# Lesson_05.net
KiCad netlist of a schematic drawn in Altium Designer
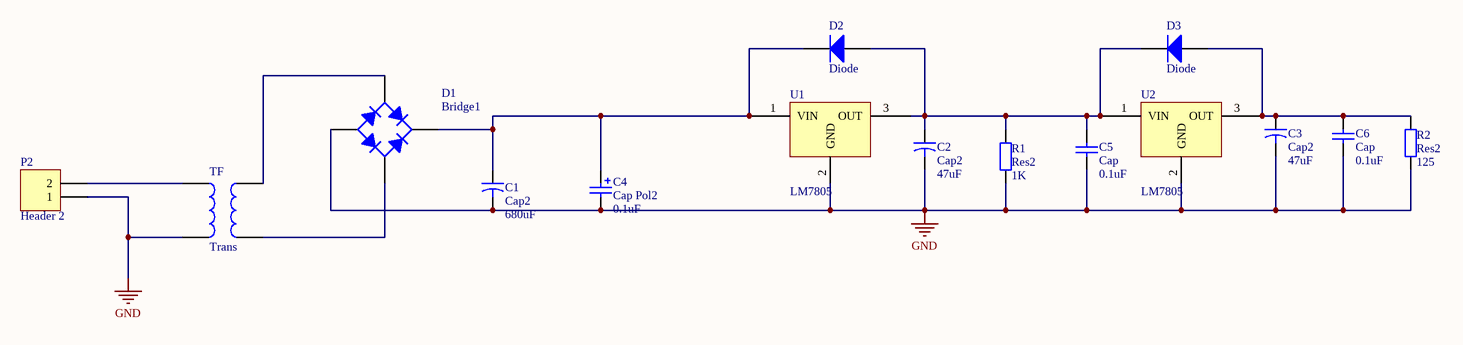
[diagram p0: Lesson_05.SchDoc]

(export (version "E")
  (design (tool "Eeschema 10.0.6"))
  (components
    (comp (ref "C1")
      (value "Cap2")
      (footprint "CAPR5-4X5")
      (description "Capacitor")
      (fields (field (name "ALTIUM_VALUE") "680uF") (field (name "PUBLISHER") "Altium Limited"))
      (libsource (lib "Miscellaneous Devices") (part "Cap2"))
    )
    (comp (ref "C2")
      (value "Cap2")
      (footprint "CAPR5-4X5")
      (description "Capacitor")
      (fields (field (name "ALTIUM_VALUE") "47uF") (field (name "PUBLISHER") "Altium Limited"))
      (libsource (lib "Miscellaneous Devices") (part "Cap2"))
    )
    (comp (ref "C3")
      (value "Cap2")
      (footprint "CAPR5-4X5")
      (description "Capacitor")
      (fields (field (name "ALTIUM_VALUE") "47uF") (field (name "PUBLISHER") "Altium Limited"))
      (libsource (lib "Miscellaneous Devices") (part "Cap2"))
    )
    (comp (ref "C4")
      (value "Cap Pol2")
      (footprint "POLAR0.8")
      (description "Polarized Capacitor (Axial)")
      (fields (field (name "ALTIUM_VALUE") "0.1uF") (field (name "PUBLISHER") "Altium Limited"))
      (libsource (lib "Miscellaneous Devices") (part "Cap Pol2"))
    )
    (comp (ref "C5")
      (value "Cap")
      (footprint "RAD-0.3")
      (description "Capacitor")
      (fields (field (name "ALTIUM_VALUE") "0.1uF") (field (name "PUBLISHER") "Altium Limited"))
      (libsource (lib "Miscellaneous Devices") (part "Cap"))
    )
    (comp (ref "C6")
      (value "Cap")
      (footprint "RAD-0.3")
      (description "Capacitor")
      (fields (field (name "ALTIUM_VALUE") "0.1uF") (field (name "PUBLISHER") "Altium Limited"))
      (libsource (lib "Miscellaneous Devices") (part "Cap"))
    )
    (comp (ref "D1")
      (value "Bridge1")
      (footprint "D-38")
      (description "Full Wave Diode Bridge")
      (fields (field (name "PUBLISHER") "Altium Limited"))
      (libsource (lib "Miscellaneous Devices") (part "Bridge1"))
    )
    (comp (ref "D2")
      (value "Diode")
      (footprint "SMC")
      (description "Default Diode")
      (fields (field (name "PUBLISHER") "Altium Limited"))
      (libsource (lib "Miscellaneous Devices") (part "Diode"))
    )
    (comp (ref "D3")
      (value "Diode")
      (footprint "SMC")
      (description "Default Diode")
      (fields (field (name "PUBLISHER") "Altium Limited"))
      (libsource (lib "Miscellaneous Devices") (part "Diode"))
    )
    (comp (ref "P2")
      (value "Header 2")
      (footprint "HDR1X2")
      (description "Header, 2-Pin")
      (fields (field (name "PUBLISHER") "Altium Limited"))
      (libsource (lib "Miscellaneous Connectors") (part "Header 2"))
    )
    (comp (ref "R1")
      (value "Res2")
      (footprint "AXIAL-0.4")
      (description "Resistor")
      (fields (field (name "ALTIUM_VALUE") "1K") (field (name "PUBLISHER") "Altium Limited"))
      (libsource (lib "Miscellaneous Devices") (part "Res2"))
    )
    (comp (ref "R2")
      (value "Res2")
      (footprint "AXIAL-0.4")
      (description "Resistor")
      (fields (field (name "ALTIUM_VALUE") "125") (field (name "PUBLISHER") "Altium Limited"))
      (libsource (lib "Miscellaneous Devices") (part "Res2"))
    )
    (comp (ref "TF")
      (value "Trans")
      (footprint "TRANS")
      (description "Transformer")
      (fields (field (name "PUBLISHER") "Altium Limited"))
      (libsource (lib "Miscellaneous Devices") (part "Trans"))
    )
    (comp (ref "U1")
      (value "LM7805")
      (footprint "LM7805-TO220 - duplicate")
      (libsource (lib "MIC5219") (part "LM7805"))
    )
    (comp (ref "U2")
      (value "LM7805")
      (footprint "LM7805-TO220 - duplicate")
      (libsource (lib "MIC5219") (part "LM7805"))
    )
  )
  (nets
    (net (code "1") (name "GND") (class "Default")
      (node (ref "C1") (pin "2") (pinfunction "2_2") (pintype "passive"))
      (node (ref "C2") (pin "2") (pinfunction "2_2") (pintype "passive"))
      (node (ref "C3") (pin "2") (pinfunction "2_2") (pintype "passive"))
      (node (ref "C4") (pin "2") (pinfunction "2_2") (pintype "passive"))
      (node (ref "C5") (pin "1") (pinfunction "1_1") (pintype "passive"))
      (node (ref "C6") (pin "1") (pinfunction "1_1") (pintype "passive"))
      (node (ref "D1") (pin "3") (pinfunction "A_3") (pintype "passive"))
      (node (ref "P2") (pin "1") (pinfunction "1_1") (pintype "passive"))
      (node (ref "R1") (pin "1") (pinfunction "1_1") (pintype "passive"))
      (node (ref "R2") (pin "1") (pinfunction "1_1") (pintype "passive"))
      (node (ref "TF") (pin "2") (pinfunction "2_2") (pintype "passive"))
      (node (ref "U1") (pin "2") (pinfunction "GND_2") (pintype "passive"))
      (node (ref "U2") (pin "2") (pinfunction "GND_2") (pintype "passive"))
    )
    (net (code "2") (name "Net-(D1-C-Pad2)") (class "Default")
      (node (ref "D1") (pin "2") (pinfunction "C_2") (pintype "passive"))
      (node (ref "TF") (pin "4") (pinfunction "4_4") (pintype "passive"))
    )
    (net (code "3") (name "Net-(D1-C-Pad4)") (class "Default")
      (node (ref "D1") (pin "4") (pinfunction "C_4") (pintype "passive"))
      (node (ref "TF") (pin "3") (pinfunction "3_3") (pintype "passive"))
    )
    (net (code "4") (name "Net-(D1-K)") (class "Default")
      (node (ref "C1") (pin "1") (pinfunction "1_1") (pintype "passive"))
      (node (ref "C4") (pin "1") (pinfunction "1_1") (pintype "passive"))
      (node (ref "D1") (pin "1") (pinfunction "K_1") (pintype "passive"))
      (node (ref "D2") (pin "2") (pinfunction "K_2") (pintype "passive"))
      (node (ref "U1") (pin "1") (pinfunction "VIN_1") (pintype "passive"))
    )
    (net (code "5") (name "Net-(D2-A)") (class "Default")
      (node (ref "C2") (pin "1") (pinfunction "1_1") (pintype "passive"))
      (node (ref "C5") (pin "2") (pinfunction "2_2") (pintype "passive"))
      (node (ref "D2") (pin "1") (pinfunction "A_1") (pintype "passive"))
      (node (ref "D3") (pin "2") (pinfunction "K_2") (pintype "passive"))
      (node (ref "R1") (pin "2") (pinfunction "2_2") (pintype "passive"))
      (node (ref "U1") (pin "3") (pinfunction "OUT_3") (pintype "passive"))
      (node (ref "U2") (pin "1") (pinfunction "VIN_1") (pintype "passive"))
    )
    (net (code "6") (name "Net-(D3-A)") (class "Default")
      (node (ref "C3") (pin "1") (pinfunction "1_1") (pintype "passive"))
      (node (ref "C6") (pin "2") (pinfunction "2_2") (pintype "passive"))
      (node (ref "D3") (pin "1") (pinfunction "A_1") (pintype "passive"))
      (node (ref "R2") (pin "2") (pinfunction "2_2") (pintype "passive"))
      (node (ref "U2") (pin "3") (pinfunction "OUT_3") (pintype "passive"))
    )
    (net (code "7") (name "Net-(P2-Pad2)") (class "Default")
      (node (ref "P2") (pin "2") (pinfunction "2_2") (pintype "passive"))
      (node (ref "TF") (pin "1") (pinfunction "1_1") (pintype "passive"))
    )
  )
)
